# esquem_tico.net
KiCad netlist of a schematic drawn in EAGLE
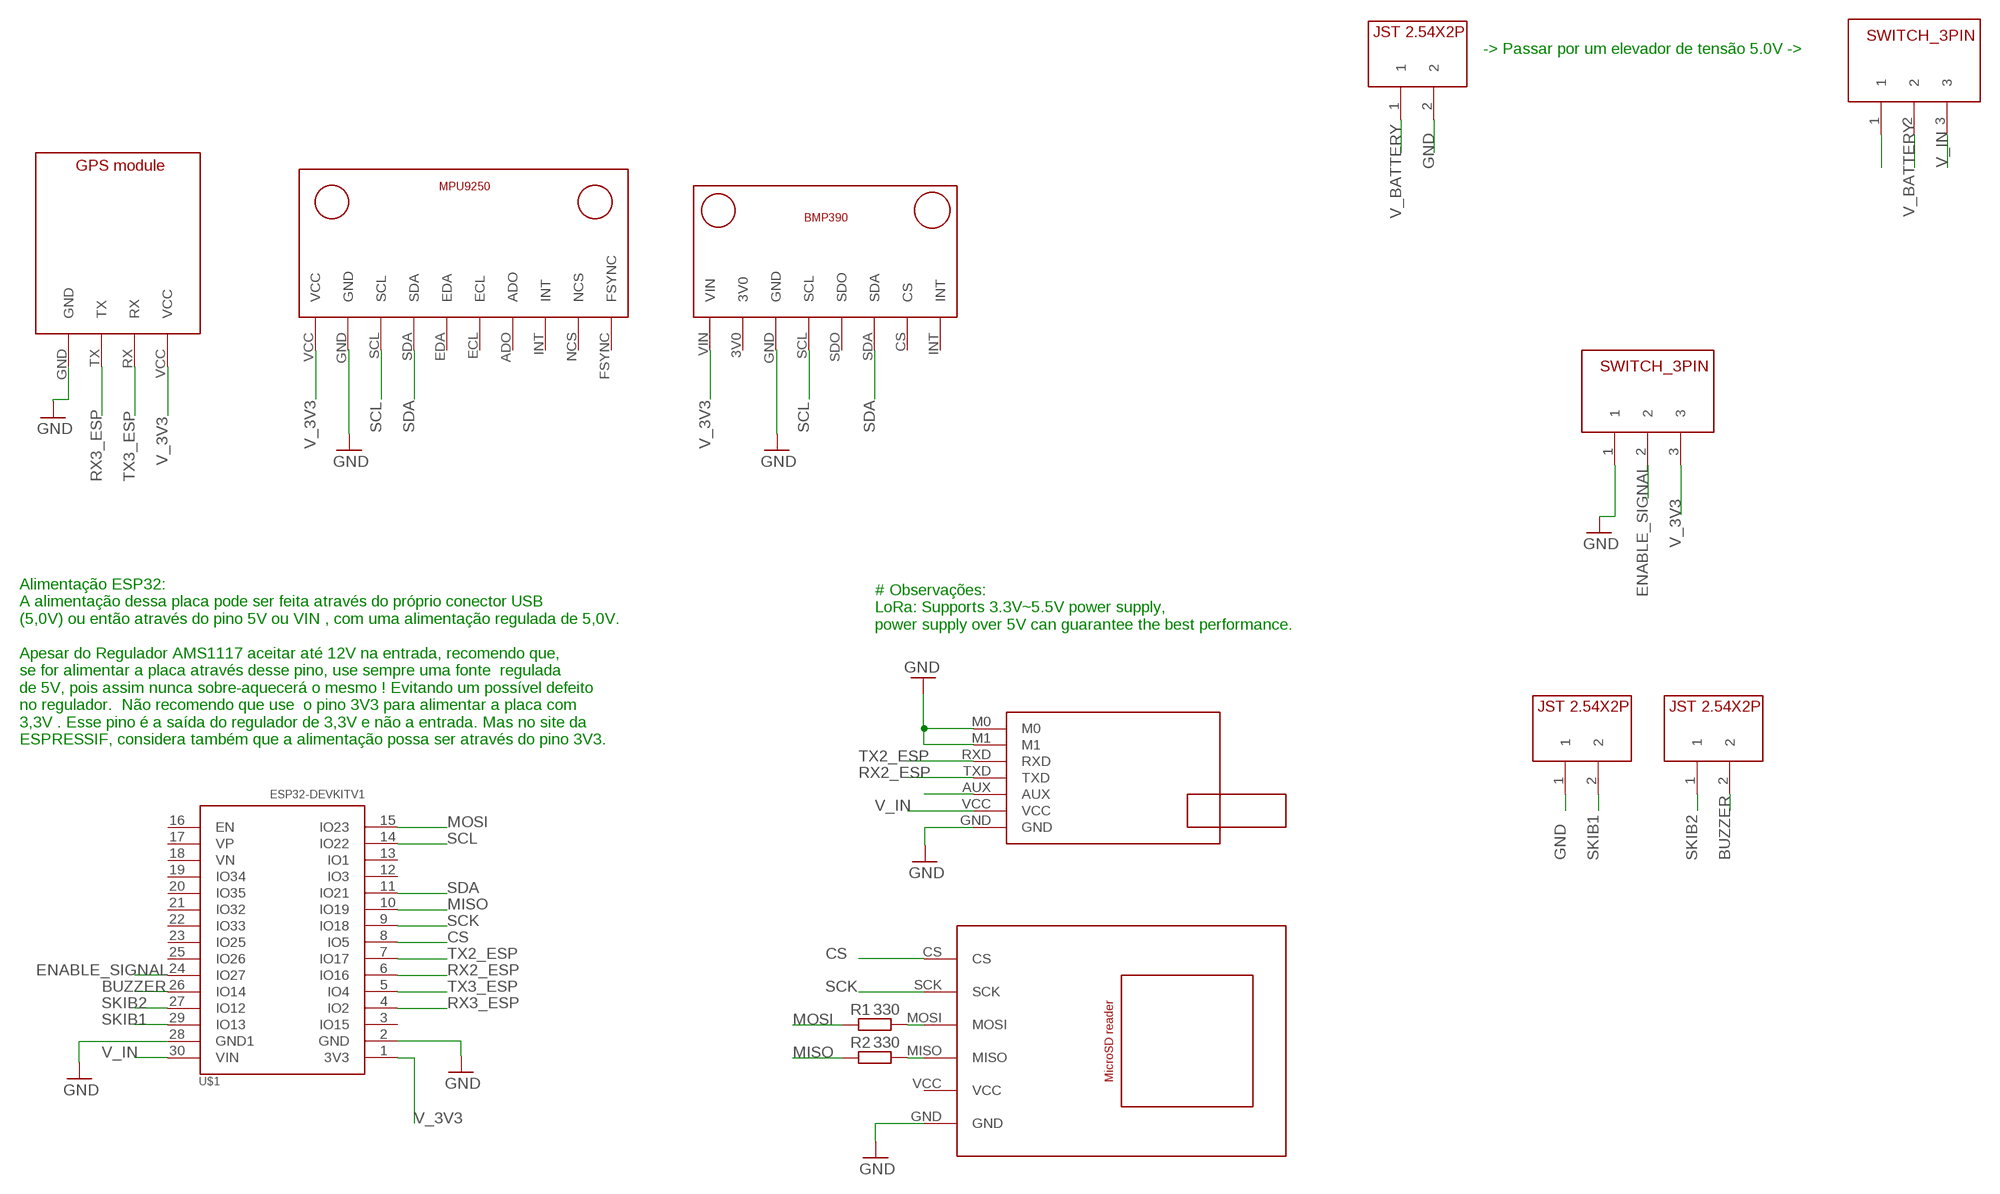
[diagram p0: schematic, sheet 1]

(export (version "E")
  (design (tool "Eeschema 10.0.6"))
  (components
    (comp (ref "R1")
      (value "330")
      (footprint "eagle-import:0207_10")
      (libsource (lib "eagle-import") (part "R-EU_0207/10"))
    )
    (comp (ref "R2")
      (value "330")
      (footprint "eagle-import:0207_10")
      (libsource (lib "eagle-import") (part "R-EU_0207/10"))
    )
    (comp (ref "U$1")
      (value "ESP32DEVKITV1")
      (footprint "eagle-import:ESP32-DEVKITV1")
      (libsource (lib "eagle-import") (part "ESP32DEVKITV1"))
    )
    (comp (ref "U$2")
      (value "E22-400T30D")
      (footprint "eagle-import:E22-400T30D_FOOTPRINT")
      (libsource (lib "eagle-import") (part "E22-400T30D"))
    )
    (comp (ref "U$3")
      (value "GPS_MODULE")
      (footprint "eagle-import:GPS_MODULE_FOOTPRINT")
      (libsource (lib "eagle-import") (part "GPS_MODULE"))
    )
    (comp (ref "U$5")
      (value "BMP390V1")
      (footprint "eagle-import:BMP390_FOOTPRINT")
      (libsource (lib "eagle-import") (part "BMP390V1"))
    )
    (comp (ref "U$6")
      (value "MPU9250V1")
      (footprint "eagle-import:MPU9250_FOOTPRINT")
      (libsource (lib "eagle-import") (part "MPU9250V1"))
    )
    (comp (ref "U$7")
      (value "MICROSD_READER")
      (footprint "eagle-import:MICROSD_READER_FOOTPRINT")
      (libsource (lib "eagle-import") (part "MICROSD_READER"))
    )
    (comp (ref "U$8")
      (value "JST2.54X2P")
      (footprint "eagle-import:JST2.54X2P_FOOTPRINT")
      (libsource (lib "eagle-import") (part "JST2.54X2P"))
    )
    (comp (ref "U$9")
      (value "JST2.54X2P")
      (footprint "eagle-import:JST2.54X2P_FOOTPRINT")
      (libsource (lib "eagle-import") (part "JST2.54X2P"))
    )
    (comp (ref "U$10")
      (value "SWITCH_3PIN")
      (footprint "eagle-import:SWITCH_3PIN")
      (libsource (lib "eagle-import") (part "SWITCH_3PIN"))
    )
    (comp (ref "U$11")
      (value "SWITCH_3PIN")
      (footprint "eagle-import:SWITCH_3PIN")
      (libsource (lib "eagle-import") (part "SWITCH_3PIN"))
    )
    (comp (ref "U$12")
      (value "JST2.54X2P")
      (footprint "eagle-import:JST2.54X2P_FOOTPRINT")
      (libsource (lib "eagle-import") (part "JST2.54X2P"))
    )
  )
  (nets
    (net (code "1") (name "/BUZZER") (class "Default")
      (node (ref "U$1") (pin "26") (pinfunction "IO14_26") (pintype "bidirectional"))
      (node (ref "U$9") (pin "2") (pinfunction "2_2") (pintype "bidirectional"))
    )
    (net (code "2") (name "/CS") (class "Default")
      (node (ref "U$1") (pin "8") (pinfunction "IO5_8") (pintype "bidirectional"))
      (node (ref "U$7") (pin "CS") (pinfunction "CS_CS") (pintype "bidirectional"))
    )
    (net (code "3") (name "/ENABLE_SIGNAL") (class "Default")
      (node (ref "U$1") (pin "24") (pinfunction "IO27_24") (pintype "bidirectional"))
      (node (ref "U$10") (pin "2") (pinfunction "2_2") (pintype "bidirectional"))
    )
    (net (code "4") (name "/MISO") (class "Default")
      (node (ref "R2") (pin "1") (pinfunction "1_1") (pintype "passive"))
      (node (ref "U$1") (pin "10") (pinfunction "IO19_10") (pintype "bidirectional"))
    )
    (net (code "5") (name "/MOSI") (class "Default")
      (node (ref "R1") (pin "1") (pinfunction "1_1") (pintype "passive"))
      (node (ref "U$1") (pin "15") (pinfunction "IO23_15") (pintype "bidirectional"))
    )
    (net (code "6") (name "/RX2_ESP") (class "Default")
      (node (ref "U$1") (pin "6") (pinfunction "IO16_6") (pintype "bidirectional"))
      (node (ref "U$2") (pin "TXD") (pinfunction "TXD_TXD") (pintype "bidirectional"))
    )
    (net (code "7") (name "/RX3_ESP") (class "Default")
      (node (ref "U$1") (pin "4") (pinfunction "IO2_4") (pintype "bidirectional"))
      (node (ref "U$3") (pin "TX") (pinfunction "TX_TX") (pintype "bidirectional"))
    )
    (net (code "8") (name "/SCK") (class "Default")
      (node (ref "U$1") (pin "9") (pinfunction "IO18_9") (pintype "bidirectional"))
      (node (ref "U$7") (pin "SCK") (pinfunction "SCK_SCK") (pintype "bidirectional"))
    )
    (net (code "9") (name "/SCL") (class "Default")
      (node (ref "U$1") (pin "14") (pinfunction "IO22_14") (pintype "bidirectional"))
      (node (ref "U$5") (pin "SCL") (pinfunction "SCL_SCL") (pintype "bidirectional"))
      (node (ref "U$6") (pin "SCL") (pinfunction "SCL_SCL") (pintype "bidirectional"))
    )
    (net (code "10") (name "/SDA") (class "Default")
      (node (ref "U$1") (pin "11") (pinfunction "IO21_11") (pintype "bidirectional"))
      (node (ref "U$5") (pin "SDA") (pinfunction "SDA_SDA") (pintype "bidirectional"))
      (node (ref "U$6") (pin "SDA") (pinfunction "SDA_SDA") (pintype "bidirectional"))
    )
    (net (code "11") (name "/SKIB1") (class "Default")
      (node (ref "U$1") (pin "29") (pinfunction "IO13_29") (pintype "bidirectional"))
      (node (ref "U$8") (pin "2") (pinfunction "2_2") (pintype "bidirectional"))
    )
    (net (code "12") (name "/SKIB2") (class "Default")
      (node (ref "U$1") (pin "27") (pinfunction "IO12_27") (pintype "bidirectional"))
      (node (ref "U$9") (pin "1") (pinfunction "1_1") (pintype "bidirectional"))
    )
    (net (code "13") (name "/TX2_ESP") (class "Default")
      (node (ref "U$1") (pin "7") (pinfunction "IO17_7") (pintype "bidirectional"))
      (node (ref "U$2") (pin "RXD") (pinfunction "RXD_RXD") (pintype "bidirectional"))
    )
    (net (code "14") (name "/TX3_ESP") (class "Default")
      (node (ref "U$1") (pin "5") (pinfunction "IO4_5") (pintype "bidirectional"))
      (node (ref "U$3") (pin "RX") (pinfunction "RX_RX") (pintype "bidirectional"))
    )
    (net (code "15") (name "/V_3V3") (class "Default")
      (node (ref "U$1") (pin "1") (pinfunction "3V3_1") (pintype "bidirectional"))
      (node (ref "U$10") (pin "3") (pinfunction "3_3") (pintype "bidirectional"))
      (node (ref "U$3") (pin "VCC") (pinfunction "VCC_VCC") (pintype "bidirectional"))
      (node (ref "U$5") (pin "VIN") (pinfunction "VIN_VIN") (pintype "bidirectional"))
      (node (ref "U$6") (pin "VCC") (pinfunction "VCC_VCC") (pintype "bidirectional"))
    )
    (net (code "16") (name "/V_BATTERY") (class "Default")
      (node (ref "U$11") (pin "2") (pinfunction "2_2") (pintype "bidirectional"))
      (node (ref "U$12") (pin "1") (pinfunction "1_1") (pintype "bidirectional"))
    )
    (net (code "17") (name "/V_IN") (class "Default")
      (node (ref "U$1") (pin "30") (pinfunction "VIN_30") (pintype "bidirectional"))
      (node (ref "U$11") (pin "3") (pinfunction "3_3") (pintype "bidirectional"))
      (node (ref "U$2") (pin "VCC") (pinfunction "VCC_VCC") (pintype "bidirectional"))
    )
    (net (code "18") (name "GND") (class "Default")
      (node (ref "U$1") (pin "2") (pinfunction "GND_2") (pintype "bidirectional"))
      (node (ref "U$1") (pin "28") (pinfunction "GND1_28") (pintype "bidirectional"))
      (node (ref "U$10") (pin "1") (pinfunction "1_1") (pintype "bidirectional"))
      (node (ref "U$12") (pin "2") (pinfunction "2_2") (pintype "bidirectional"))
      (node (ref "U$2") (pin "GND") (pinfunction "GND_GND") (pintype "bidirectional"))
      (node (ref "U$2") (pin "M0") (pinfunction "M0_M0") (pintype "bidirectional"))
      (node (ref "U$2") (pin "M1") (pinfunction "M1_M1") (pintype "bidirectional"))
      (node (ref "U$3") (pin "GND") (pinfunction "GND_GND") (pintype "bidirectional"))
      (node (ref "U$5") (pin "GND") (pinfunction "GND_GND") (pintype "bidirectional"))
      (node (ref "U$6") (pin "GND") (pinfunction "GND_GND") (pintype "bidirectional"))
      (node (ref "U$7") (pin "GND") (pinfunction "GND_GND") (pintype "bidirectional"))
      (node (ref "U$8") (pin "1") (pinfunction "1_1") (pintype "bidirectional"))
    )
    (net (code "19") (name "Net-(R1-Pad2)") (class "Default")
      (node (ref "R1") (pin "2") (pinfunction "2_2") (pintype "passive"))
      (node (ref "U$7") (pin "MOSI") (pinfunction "MOSI_MOSI") (pintype "bidirectional"))
    )
    (net (code "20") (name "Net-(R2-Pad2)") (class "Default")
      (node (ref "R2") (pin "2") (pinfunction "2_2") (pintype "passive"))
      (node (ref "U$7") (pin "MISO") (pinfunction "MISO_MISO") (pintype "bidirectional"))
    )
    (net (code "21") (name "unconnected-(U$1-EN-Pad16)") (class "Default")
      (node (ref "U$1") (pin "16") (pinfunction "EN_16") (pintype "bidirectional"))
    )
    (net (code "22") (name "unconnected-(U$1-IO1-Pad13)") (class "Default")
      (node (ref "U$1") (pin "13") (pinfunction "IO1_13") (pintype "bidirectional"))
    )
    (net (code "23") (name "unconnected-(U$1-IO3-Pad12)") (class "Default")
      (node (ref "U$1") (pin "12") (pinfunction "IO3_12") (pintype "bidirectional"))
    )
    (net (code "24") (name "unconnected-(U$1-IO15-Pad3)") (class "Default")
      (node (ref "U$1") (pin "3") (pinfunction "IO15_3") (pintype "bidirectional"))
    )
    (net (code "25") (name "unconnected-(U$1-IO25-Pad23)") (class "Default")
      (node (ref "U$1") (pin "23") (pinfunction "IO25_23") (pintype "bidirectional"))
    )
    (net (code "26") (name "unconnected-(U$1-IO26-Pad25)") (class "Default")
      (node (ref "U$1") (pin "25") (pinfunction "IO26_25") (pintype "bidirectional"))
    )
    (net (code "27") (name "unconnected-(U$1-IO32-Pad21)") (class "Default")
      (node (ref "U$1") (pin "21") (pinfunction "IO32_21") (pintype "bidirectional"))
    )
    (net (code "28") (name "unconnected-(U$1-IO33-Pad22)") (class "Default")
      (node (ref "U$1") (pin "22") (pinfunction "IO33_22") (pintype "bidirectional"))
    )
    (net (code "29") (name "unconnected-(U$1-IO34-Pad19)") (class "Default")
      (node (ref "U$1") (pin "19") (pinfunction "IO34_19") (pintype "bidirectional"))
    )
    (net (code "30") (name "unconnected-(U$1-IO35-Pad20)") (class "Default")
      (node (ref "U$1") (pin "20") (pinfunction "IO35_20") (pintype "bidirectional"))
    )
    (net (code "31") (name "unconnected-(U$1-VN-Pad18)") (class "Default")
      (node (ref "U$1") (pin "18") (pinfunction "VN_18") (pintype "bidirectional"))
    )
    (net (code "32") (name "unconnected-(U$1-VP-Pad17)") (class "Default")
      (node (ref "U$1") (pin "17") (pinfunction "VP_17") (pintype "bidirectional"))
    )
    (net (code "33") (name "unconnected-(U$2-PadAUX)") (class "Default")
      (node (ref "U$2") (pin "AUX") (pinfunction "AUX_AUX") (pintype "bidirectional"))
    )
    (net (code "34") (name "unconnected-(U$5-Pad3V0)") (class "Default")
      (node (ref "U$5") (pin "3V0") (pinfunction "3V0_3V0") (pintype "bidirectional"))
    )
    (net (code "35") (name "unconnected-(U$5-PadCS)") (class "Default")
      (node (ref "U$5") (pin "CS") (pinfunction "CS_CS") (pintype "bidirectional"))
    )
    (net (code "36") (name "unconnected-(U$5-PadINT)") (class "Default")
      (node (ref "U$5") (pin "INT") (pinfunction "INT_INT") (pintype "bidirectional"))
    )
    (net (code "37") (name "unconnected-(U$5-PadSDO)") (class "Default")
      (node (ref "U$5") (pin "SDO") (pinfunction "SDO_SDO") (pintype "bidirectional"))
    )
    (net (code "38") (name "unconnected-(U$6-PadADO)") (class "Default")
      (node (ref "U$6") (pin "ADO") (pinfunction "ADO_ADO") (pintype "bidirectional"))
    )
    (net (code "39") (name "unconnected-(U$6-PadECL)") (class "Default")
      (node (ref "U$6") (pin "ECL") (pinfunction "ECL_ECL") (pintype "bidirectional"))
    )
    (net (code "40") (name "unconnected-(U$6-PadEDA)") (class "Default")
      (node (ref "U$6") (pin "EDA") (pinfunction "EDA_EDA") (pintype "bidirectional"))
    )
    (net (code "41") (name "unconnected-(U$6-PadFSYNC)") (class "Default")
      (node (ref "U$6") (pin "FSYNC") (pinfunction "FSYNC_FSYNC") (pintype "bidirectional"))
    )
    (net (code "42") (name "unconnected-(U$6-PadINT)") (class "Default")
      (node (ref "U$6") (pin "INT") (pinfunction "INT_INT") (pintype "bidirectional"))
    )
    (net (code "43") (name "unconnected-(U$6-PadNCS)") (class "Default")
      (node (ref "U$6") (pin "NCS") (pinfunction "NCS_NCS") (pintype "bidirectional"))
    )
    (net (code "44") (name "unconnected-(U$7-PadVCC)") (class "Default")
      (node (ref "U$7") (pin "VCC") (pinfunction "VCC_VCC") (pintype "bidirectional"))
    )
    (net (code "45") (name "unconnected-(U$11-Pad1)") (class "Default")
      (node (ref "U$11") (pin "1") (pinfunction "1_1") (pintype "bidirectional"))
    )
  )
)
